# soundcollector.net
KiCad netlist of a schematic drawn in Altium Designer
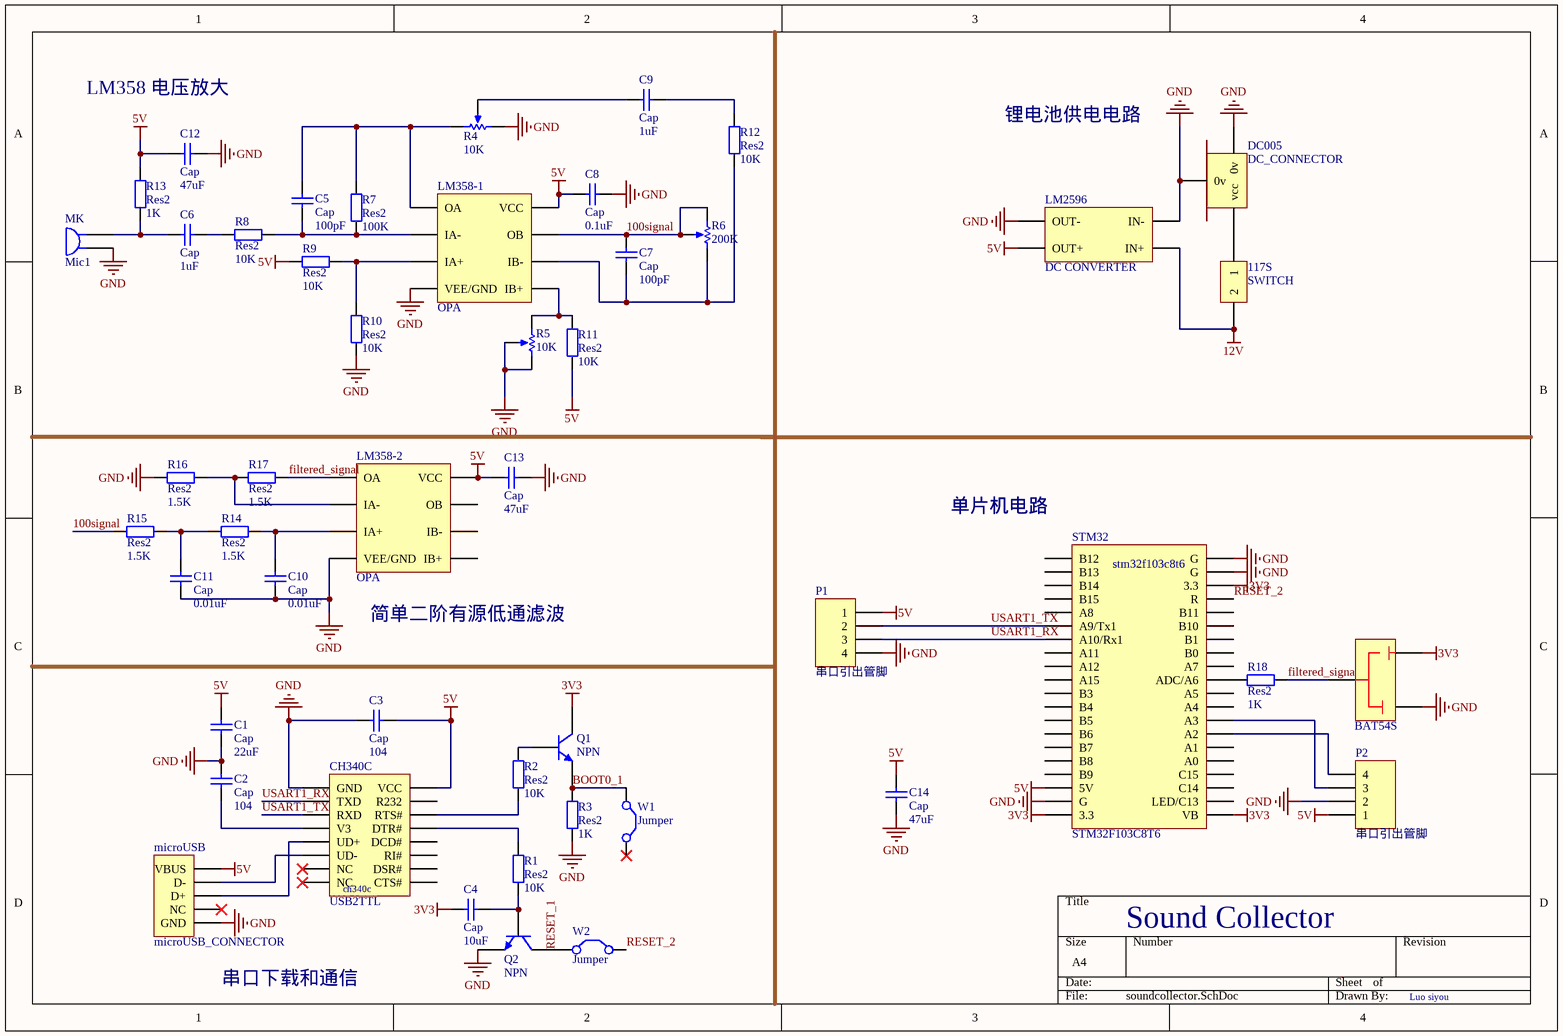
[diagram p0: soundcollector.SchDoc]

(export (version "E")
  (design (tool "Eeschema 10.0.6"))
  (components
    (comp (ref "117S")
      (value "SWITCH")
      (footprint "117S")
      (description "船形开关")
      (libsource (lib "SClib") (part "117S"))
    )
    (comp (ref "BAT54S") (value "BAT54S") (footprint "SOT-23") (libsource (lib "SClib") (part "BAT54S")))
    (comp (ref "C1")
      (value "Cap")
      (footprint "0805")
      (description "Capacitor")
      (fields (field (name "ALTIUM_VALUE") "22uF") (field (name "PUBLISHER") "Altium Limited"))
      (libsource (lib "Miscellaneous Devices") (part "Cap"))
    )
    (comp (ref "C2")
      (value "Cap")
      (footprint "0805")
      (description "Capacitor")
      (fields (field (name "ALTIUM_VALUE") "104") (field (name "PUBLISHER") "Altium Limited"))
      (libsource (lib "Miscellaneous Devices") (part "Cap"))
    )
    (comp (ref "C3")
      (value "Cap")
      (footprint "0805")
      (description "Capacitor")
      (fields (field (name "ALTIUM_VALUE") "104") (field (name "PUBLISHER") "Altium Limited"))
      (libsource (lib "Miscellaneous Devices") (part "Cap"))
    )
    (comp (ref "C4")
      (value "Cap")
      (footprint "0805")
      (description "Capacitor")
      (fields (field (name "ALTIUM_VALUE") "10uF") (field (name "PUBLISHER") "Altium Limited"))
      (libsource (lib "Miscellaneous Devices") (part "Cap"))
    )
    (comp (ref "C5")
      (value "Cap")
      (footprint "0805")
      (description "Capacitor")
      (fields (field (name "ALTIUM_VALUE") "100pF") (field (name "PUBLISHER") "Altium Limited"))
      (libsource (lib "Miscellaneous Devices") (part "Cap"))
    )
    (comp (ref "C6")
      (value "Cap")
      (footprint "0805")
      (description "Capacitor")
      (fields (field (name "ALTIUM_VALUE") "1uF") (field (name "PUBLISHER") "Altium Limited"))
      (libsource (lib "Miscellaneous Devices") (part "Cap"))
    )
    (comp (ref "C7")
      (value "Cap")
      (footprint "0805")
      (description "Capacitor")
      (fields (field (name "ALTIUM_VALUE") "100pF") (field (name "PUBLISHER") "Altium Limited"))
      (libsource (lib "Miscellaneous Devices") (part "Cap"))
    )
    (comp (ref "C8")
      (value "Cap")
      (footprint "0805")
      (description "Capacitor")
      (fields (field (name "ALTIUM_VALUE") "0.1uF") (field (name "PUBLISHER") "Altium Limited"))
      (libsource (lib "Miscellaneous Devices") (part "Cap"))
    )
    (comp (ref "C9")
      (value "Cap")
      (footprint "0805")
      (description "Capacitor")
      (fields (field (name "ALTIUM_VALUE") "1uF") (field (name "PUBLISHER") "Altium Limited"))
      (libsource (lib "Miscellaneous Devices") (part "Cap"))
    )
    (comp (ref "C10")
      (value "Cap")
      (footprint "0805")
      (description "Capacitor")
      (fields (field (name "ALTIUM_VALUE") "0.01uF") (field (name "PUBLISHER") "Altium Limited"))
      (libsource (lib "Miscellaneous Devices") (part "Cap"))
    )
    (comp (ref "C11")
      (value "Cap")
      (footprint "0805")
      (description "Capacitor")
      (fields (field (name "ALTIUM_VALUE") "0.01uF") (field (name "PUBLISHER") "Altium Limited"))
      (libsource (lib "Miscellaneous Devices") (part "Cap"))
    )
    (comp (ref "C12")
      (value "Cap")
      (footprint "0805")
      (description "Capacitor")
      (fields (field (name "ALTIUM_VALUE") "47uF") (field (name "PUBLISHER") "Altium Limited"))
      (libsource (lib "Miscellaneous Devices") (part "Cap"))
    )
    (comp (ref "C13")
      (value "Cap")
      (footprint "0805")
      (description "Capacitor")
      (fields (field (name "ALTIUM_VALUE") "47uF") (field (name "PUBLISHER") "Altium Limited"))
      (libsource (lib "Miscellaneous Devices") (part "Cap"))
    )
    (comp (ref "C14")
      (value "Cap")
      (footprint "0805")
      (description "Capacitor")
      (fields (field (name "ALTIUM_VALUE") "47uF") (field (name "PUBLISHER") "Altium Limited"))
      (libsource (lib "Miscellaneous Devices") (part "Cap"))
    )
    (comp (ref "CH340C")
      (value "USB2TTL")
      (footprint "SOP16")
      (description "电平转换芯片")
      (libsource (lib "SClib") (part "CH340"))
    )
    (comp (ref "DC005")
      (value "DC_CONNECTOR")
      (footprint "DC005")
      (description "直流电源插座")
      (libsource (lib "SClib") (part "DC005"))
    )
    (comp (ref "LM358-1")
      (value "OPA")
      (footprint "SOP-8")
      (description "集成运放")
      (libsource (lib "SClib") (part "LM358"))
    )
    (comp (ref "LM358-2")
      (value "OPA")
      (footprint "SOP-8")
      (description "集成运放")
      (libsource (lib "SClib") (part "LM358"))
    )
    (comp (ref "LM2596")
      (value "DC CONVERTER")
      (footprint "LM2596S")
      (description "直流降压模块")
      (libsource (lib "SClib") (part "LM2596"))
    )
    (comp (ref "microUSB")
      (value "microUSB_CONNECTOR")
      (footprint "MicroUSB-SIP-5")
      (description "将microUSB转换成SIP接口")
      (libsource (lib "SClib") (part "microUSB"))
    )
    (comp (ref "MK")
      (value "Mic1")
      (footprint "PIN2")
      (description "Microphone")
      (fields (field (name "PUBLISHER") "Altium Limited"))
      (libsource (lib "Miscellaneous Devices") (part "Mic1"))
    )
    (comp (ref "P1")
      (value "串口引出管脚")
      (footprint "HDR1X4")
      (description "Header, 4-Pin")
      (fields (field (name "PUBLISHER") "Altium Limited"))
      (libsource (lib "Miscellaneous Connectors") (part "Header 4"))
    )
    (comp (ref "P2")
      (value "串口引出管脚")
      (footprint "HDR1X4")
      (description "Header, 4-Pin")
      (fields (field (name "PUBLISHER") "Altium Limited"))
      (libsource (lib "") (part "Header 4_1"))
    )
    (comp (ref "Q1")
      (value "NPN")
      (footprint "SOT-23")
      (description "NPN三极管")
      (libsource (lib "SClib") (part "S8050"))
    )
    (comp (ref "Q2")
      (value "NPN")
      (footprint "SOT-23")
      (description "NPN三极管")
      (libsource (lib "SClib") (part "S8050"))
    )
    (comp (ref "R1")
      (value "Res2")
      (footprint "0805")
      (description "Resistor")
      (fields (field (name "ALTIUM_VALUE") "10K") (field (name "PUBLISHER") "Altium Limited"))
      (libsource (lib "Miscellaneous Devices") (part "Res2"))
    )
    (comp (ref "R2")
      (value "Res2")
      (footprint "0805")
      (description "Resistor")
      (fields (field (name "ALTIUM_VALUE") "10K") (field (name "PUBLISHER") "Altium Limited"))
      (libsource (lib "Miscellaneous Devices") (part "Res2"))
    )
    (comp (ref "R3")
      (value "Res2")
      (footprint "0805")
      (description "Resistor")
      (fields (field (name "ALTIUM_VALUE") "1K") (field (name "PUBLISHER") "Altium Limited"))
      (libsource (lib "Miscellaneous Devices") (part "Res2"))
    )
    (comp (ref "R4") (value "10K") (footprint "3296W") (libsource (lib "SClib") (part "RPOT")))
    (comp (ref "R5") (value "10K") (footprint "3296W") (libsource (lib "SClib") (part "RPOT")))
    (comp (ref "R6") (value "200K") (footprint "3296W") (libsource (lib "SClib") (part "RPOT")))
    (comp (ref "R7")
      (value "Res2")
      (footprint "0805")
      (description "Resistor")
      (fields (field (name "ALTIUM_VALUE") "100K") (field (name "PUBLISHER") "Altium Limited"))
      (libsource (lib "Miscellaneous Devices") (part "Res2"))
    )
    (comp (ref "R8")
      (value "Res2")
      (footprint "0805")
      (description "Resistor")
      (fields (field (name "ALTIUM_VALUE") "10K") (field (name "PUBLISHER") "Altium Limited"))
      (libsource (lib "Miscellaneous Devices") (part "*"))
    )
    (comp (ref "R9")
      (value "Res2")
      (footprint "0805")
      (description "Resistor")
      (fields (field (name "ALTIUM_VALUE") "10K") (field (name "PUBLISHER") "Altium Limited"))
      (libsource (lib "") (part "Res2_1"))
    )
    (comp (ref "R10")
      (value "Res2")
      (footprint "0805")
      (description "Resistor")
      (fields (field (name "ALTIUM_VALUE") "10K") (field (name "PUBLISHER") "Altium Limited"))
      (libsource (lib "Miscellaneous Devices") (part "Res2"))
    )
    (comp (ref "R11")
      (value "Res2")
      (footprint "0805")
      (description "Resistor")
      (fields (field (name "ALTIUM_VALUE") "10K") (field (name "PUBLISHER") "Altium Limited"))
      (libsource (lib "Miscellaneous Devices") (part "Res2"))
    )
    (comp (ref "R12")
      (value "Res2")
      (footprint "0805")
      (description "Resistor")
      (fields (field (name "ALTIUM_VALUE") "10K") (field (name "PUBLISHER") "Altium Limited"))
      (libsource (lib "Miscellaneous Devices") (part "Res2"))
    )
    (comp (ref "R13")
      (value "Res2")
      (footprint "0805")
      (description "Resistor")
      (fields (field (name "ALTIUM_VALUE") "1K") (field (name "PUBLISHER") "Altium Limited"))
      (libsource (lib "Miscellaneous Devices") (part "Res2"))
    )
    (comp (ref "R14")
      (value "Res2")
      (footprint "0805")
      (description "Resistor")
      (fields (field (name "ALTIUM_VALUE") "1.5K") (field (name "PUBLISHER") "Altium Limited"))
      (libsource (lib "") (part "Res2_2"))
    )
    (comp (ref "R15")
      (value "Res2")
      (footprint "0805")
      (description "Resistor")
      (fields (field (name "ALTIUM_VALUE") "1.5K") (field (name "PUBLISHER") "Altium Limited"))
      (libsource (lib "") (part "Res2_1"))
    )
    (comp (ref "R16")
      (value "Res2")
      (footprint "0805")
      (description "Resistor")
      (fields (field (name "ALTIUM_VALUE") "1.5K") (field (name "PUBLISHER") "Altium Limited"))
      (libsource (lib "") (part "Res2_1"))
    )
    (comp (ref "R17")
      (value "Res2")
      (footprint "0805")
      (description "Resistor")
      (fields (field (name "ALTIUM_VALUE") "1.5K") (field (name "PUBLISHER") "Altium Limited"))
      (libsource (lib "") (part "Res2_2"))
    )
    (comp (ref "R18")
      (value "Res2")
      (footprint "0805")
      (description "Resistor")
      (fields (field (name "ALTIUM_VALUE") "1K") (field (name "PUBLISHER") "Altium Limited"))
      (libsource (lib "") (part "Res2_1"))
    )
    (comp (ref "STM32")
      (value "STM32F103C8T6")
      (footprint "MCU")
      (description "单片机最小系统")
      (libsource (lib "SClib") (part "STM32"))
    )
    (comp (ref "W1")
      (value "Jumper")
      (footprint "HDR1X2")
      (description "Jumper Wire")
      (fields (field (name "PUBLISHER") "Altium Limited"))
      (libsource (lib "Miscellaneous Devices") (part "Jumper"))
    )
    (comp (ref "W2")
      (value "Jumper")
      (footprint "HDR1X2")
      (description "Jumper Wire")
      (fields (field (name "PUBLISHER") "Altium Limited"))
      (libsource (lib "Miscellaneous Devices") (part "Jumper"))
    )
  )
  (nets
    (net (code "1") (name "/100signal") (class "Default")
      (node (ref "C7") (pin "2") (pinfunction "2_2") (pintype "passive"))
      (node (ref "LM358-1") (pin "7") (pinfunction "OB_7") (pintype "passive"))
      (node (ref "R15") (pin "1") (pinfunction "1_1") (pintype "passive"))
      (node (ref "R6") (pin "1") (pinfunction "TOP_1") (pintype "passive"))
      (node (ref "R6") (pin "2") (pinfunction "TAP_2") (pintype "passive"))
    )
    (net (code "2") (name "/BOOT0_1") (class "Default")
      (node (ref "Q1") (pin "2") (pinfunction "E_2") (pintype "passive"))
      (node (ref "R3") (pin "2") (pinfunction "2_2") (pintype "passive"))
      (node (ref "W1") (pin "1") (pinfunction "C1_1") (pintype "passive"))
    )
    (net (code "3") (name "/RESET_1") (class "Default")
      (node (ref "Q2") (pin "3") (pinfunction "C_3") (pintype "passive"))
      (node (ref "W2") (pin "1") (pinfunction "C1_1") (pintype "passive"))
    )
    (net (code "4") (name "/RESET_2") (class "Default")
      (node (ref "STM32") (pin "37") (pinfunction "R_37") (pintype "passive"))
      (node (ref "W2") (pin "2") (pinfunction "C2_2") (pintype "passive"))
    )
    (net (code "5") (name "/USART1_RX") (class "Default")
      (node (ref "CH340C") (pin "2") (pinfunction "TXD_2") (pintype "passive"))
      (node (ref "P1") (pin "3") (pinfunction "3_3") (pintype "passive"))
      (node (ref "STM32") (pin "7") (pinfunction "A10/Rx1_7") (pintype "passive"))
    )
    (net (code "6") (name "/USART1_TX") (class "Default")
      (node (ref "CH340C") (pin "3") (pinfunction "RXD_3") (pintype "passive"))
      (node (ref "P1") (pin "2") (pinfunction "2_2") (pintype "passive"))
      (node (ref "STM32") (pin "6") (pinfunction "A9/Tx1_6") (pintype "passive"))
    )
    (net (code "7") (name "/filtered_signal") (class "Default")
      (node (ref "BAT54S") (pin "3") (pinfunction "series_3") (pintype "passive"))
      (node (ref "LM358-2") (pin "1") (pinfunction "OA_1") (pintype "passive"))
      (node (ref "R17") (pin "1") (pinfunction "1_1") (pintype "passive"))
      (node (ref "R18") (pin "2") (pinfunction "2_2") (pintype "passive"))
    )
    (net (code "8") (name "3V3") (class "Default")
      (node (ref "BAT54S") (pin "2") (pinfunction "VCC_2") (pintype "passive"))
      (node (ref "C4") (pin "1") (pinfunction "1_1") (pintype "passive"))
      (node (ref "Q1") (pin "3") (pinfunction "C_3") (pintype "passive"))
      (node (ref "STM32") (pin "20") (pinfunction "3.3_20") (pintype "passive"))
      (node (ref "STM32") (pin "21") (pinfunction "VB_21") (pintype "passive"))
      (node (ref "STM32") (pin "38") (pinfunction "3.3_38") (pintype "passive"))
    )
    (net (code "9") (name "5V") (class "Default")
      (node (ref "C1") (pin "2") (pinfunction "2_2") (pintype "passive"))
      (node (ref "C12") (pin "1") (pinfunction "1_1") (pintype "passive"))
      (node (ref "C13") (pin "1") (pinfunction "1_1") (pintype "passive"))
      (node (ref "C14") (pin "2") (pinfunction "2_2") (pintype "passive"))
      (node (ref "C3") (pin "2") (pinfunction "2_2") (pintype "passive"))
      (node (ref "C8") (pin "1") (pinfunction "1_1") (pintype "passive"))
      (node (ref "CH340C") (pin "16") (pinfunction "VCC_16") (pintype "passive"))
      (node (ref "LM2596") (pin "3") (pinfunction "OUT+_3") (pintype "passive"))
      (node (ref "LM358-1") (pin "8") (pinfunction "VCC_8") (pintype "passive"))
      (node (ref "LM358-2") (pin "8") (pinfunction "VCC_8") (pintype "passive"))
      (node (ref "P1") (pin "1") (pinfunction "1_1") (pintype "passive"))
      (node (ref "P2") (pin "1") (pinfunction "1_1") (pintype "passive"))
      (node (ref "R11") (pin "1") (pinfunction "1_1") (pintype "passive"))
      (node (ref "R13") (pin "2") (pinfunction "2_2") (pintype "passive"))
      (node (ref "R9") (pin "1") (pinfunction "1_1") (pintype "passive"))
      (node (ref "STM32") (pin "18") (pinfunction "5V_18") (pintype "passive"))
      (node (ref "microUSB") (pin "1") (pinfunction "VBUS_1") (pintype "passive"))
    )
    (net (code "10") (name "12V") (class "Default")
      (node (ref "117S") (pin "2") (pinfunction "2_2") (pintype "passive"))
      (node (ref "LM2596") (pin "2") (pinfunction "IN+_2") (pintype "passive"))
    )
    (net (code "11") (name "GND") (class "Default")
      (node (ref "BAT54S") (pin "1") (pinfunction "GND_1") (pintype "passive"))
      (node (ref "C1") (pin "1") (pinfunction "1_1") (pintype "passive"))
      (node (ref "C10") (pin "1") (pinfunction "1_1") (pintype "passive"))
      (node (ref "C11") (pin "1") (pinfunction "1_1") (pintype "passive"))
      (node (ref "C12") (pin "2") (pinfunction "2_2") (pintype "passive"))
      (node (ref "C13") (pin "2") (pinfunction "2_2") (pintype "passive"))
      (node (ref "C14") (pin "1") (pinfunction "1_1") (pintype "passive"))
      (node (ref "C2") (pin "2") (pinfunction "2_2") (pintype "passive"))
      (node (ref "C3") (pin "1") (pinfunction "1_1") (pintype "passive"))
      (node (ref "C8") (pin "2") (pinfunction "2_2") (pintype "passive"))
      (node (ref "CH340C") (pin "1") (pinfunction "GND_1") (pintype "passive"))
      (node (ref "DC005") (pin "1") (pinfunction "0v_1") (pintype "passive"))
      (node (ref "DC005") (pin "2") (pinfunction "0v_2") (pintype "passive"))
      (node (ref "LM2596") (pin "1") (pinfunction "IN-_1") (pintype "passive"))
      (node (ref "LM2596") (pin "4") (pinfunction "OUT-_4") (pintype "passive"))
      (node (ref "LM358-1") (pin "4") (pinfunction "VEE/GND_4") (pintype "passive"))
      (node (ref "LM358-2") (pin "4") (pinfunction "VEE/GND_4") (pintype "passive"))
      (node (ref "MK") (pin "1") (pinfunction "1_1") (pintype "passive"))
      (node (ref "P1") (pin "4") (pinfunction "4_4") (pintype "passive"))
      (node (ref "P2") (pin "2") (pinfunction "2_2") (pintype "passive"))
      (node (ref "Q2") (pin "2") (pinfunction "E_2") (pintype "passive"))
      (node (ref "R10") (pin "1") (pinfunction "1_1") (pintype "passive"))
      (node (ref "R16") (pin "1") (pinfunction "1_1") (pintype "passive"))
      (node (ref "R3") (pin "1") (pinfunction "1_1") (pintype "passive"))
      (node (ref "R4") (pin "1") (pinfunction "TOP_1") (pintype "passive"))
      (node (ref "R5") (pin "2") (pinfunction "TAP_2") (pintype "passive"))
      (node (ref "R5") (pin "3") (pinfunction "BOT_3") (pintype "passive"))
      (node (ref "STM32") (pin "19") (pinfunction "G_19") (pintype "passive"))
      (node (ref "STM32") (pin "39") (pinfunction "G_39") (pintype "passive"))
      (node (ref "STM32") (pin "40") (pinfunction "G_40") (pintype "passive"))
      (node (ref "microUSB") (pin "5") (pinfunction "GND_5") (pintype "passive"))
    )
    (net (code "12") (name "Net-(C6-Pad1)") (class "Default")
      (node (ref "C6") (pin "1") (pinfunction "1_1") (pintype "passive"))
      (node (ref "MK") (pin "2") (pinfunction "2_2") (pintype "passive"))
      (node (ref "R13") (pin "1") (pinfunction "1_1") (pintype "passive"))
    )
    (net (code "13") (name "Net-(C6-Pad2)") (class "Default")
      (node (ref "C6") (pin "2") (pinfunction "2_2") (pintype "passive"))
      (node (ref "R8") (pin "1") (pinfunction "1_1") (pintype "passive"))
    )
    (net (code "14") (name "Net-(C9-Pad2)") (class "Default")
      (node (ref "C9") (pin "2") (pinfunction "2_2") (pintype "passive"))
      (node (ref "R12") (pin "2") (pinfunction "2_2") (pintype "passive"))
    )
    (net (code "15") (name "Net-(C11-Pad2)") (class "Default")
      (node (ref "C11") (pin "2") (pinfunction "2_2") (pintype "passive"))
      (node (ref "R14") (pin "2") (pinfunction "2_2") (pintype "passive"))
      (node (ref "R15") (pin "2") (pinfunction "2_2") (pintype "passive"))
    )
    (net (code "16") (name "Net-(CH340C-DTR#)") (class "Default")
      (node (ref "CH340C") (pin "13") (pinfunction "DTR#_13") (pintype "passive"))
      (node (ref "R1") (pin "2") (pinfunction "2_2") (pintype "passive"))
    )
    (net (code "17") (name "Net-(CH340C-RTS#)") (class "Default")
      (node (ref "CH340C") (pin "14") (pinfunction "RTS#_14") (pintype "passive"))
      (node (ref "R2") (pin "1") (pinfunction "1_1") (pintype "passive"))
    )
    (net (code "18") (name "Net-(CH340C-UD+)") (class "Default")
      (node (ref "CH340C") (pin "5") (pinfunction "UD+_5") (pintype "passive"))
      (node (ref "microUSB") (pin "3") (pinfunction "D+_3") (pintype "passive"))
    )
    (net (code "19") (name "Net-(CH340C-UD-)") (class "Default")
      (node (ref "CH340C") (pin "6") (pinfunction "UD-_6") (pintype "passive"))
      (node (ref "microUSB") (pin "2") (pinfunction "D-_2") (pintype "passive"))
    )
    (net (code "20") (name "Net-(CH340C-V3)") (class "Default")
      (node (ref "C2") (pin "1") (pinfunction "1_1") (pintype "passive"))
      (node (ref "CH340C") (pin "4") (pinfunction "V3_4") (pintype "passive"))
    )
    (net (code "21") (name "Net-(DC005-vcc)") (class "Default")
      (node (ref "117S") (pin "1") (pinfunction "1_1") (pintype "passive"))
      (node (ref "DC005") (pin "3") (pinfunction "vcc_3") (pintype "passive"))
    )
    (net (code "22") (name "Net-(LM358-1-IA+)") (class "Default")
      (node (ref "LM358-1") (pin "3") (pinfunction "IA+_3") (pintype "passive"))
      (node (ref "R10") (pin "2") (pinfunction "2_2") (pintype "passive"))
      (node (ref "R9") (pin "2") (pinfunction "2_2") (pintype "passive"))
    )
    (net (code "23") (name "Net-(LM358-1-IA-)") (class "Default")
      (node (ref "C5") (pin "1") (pinfunction "1_1") (pintype "passive"))
      (node (ref "LM358-1") (pin "2") (pinfunction "IA-_2") (pintype "passive"))
      (node (ref "R7") (pin "1") (pinfunction "1_1") (pintype "passive"))
      (node (ref "R8") (pin "2") (pinfunction "2_2") (pintype "passive"))
    )
    (net (code "24") (name "Net-(LM358-1-IB+)") (class "Default")
      (node (ref "LM358-1") (pin "5") (pinfunction "IB+_5") (pintype "passive"))
      (node (ref "R11") (pin "2") (pinfunction "2_2") (pintype "passive"))
      (node (ref "R5") (pin "1") (pinfunction "TOP_1") (pintype "passive"))
    )
    (net (code "25") (name "Net-(LM358-1-IB-)") (class "Default")
      (node (ref "C7") (pin "1") (pinfunction "1_1") (pintype "passive"))
      (node (ref "LM358-1") (pin "6") (pinfunction "IB-_6") (pintype "passive"))
      (node (ref "R12") (pin "1") (pinfunction "1_1") (pintype "passive"))
      (node (ref "R6") (pin "3") (pinfunction "BOT_3") (pintype "passive"))
    )
    (net (code "26") (name "Net-(LM358-1-OA)") (class "Default")
      (node (ref "C5") (pin "2") (pinfunction "2_2") (pintype "passive"))
      (node (ref "LM358-1") (pin "1") (pinfunction "OA_1") (pintype "passive"))
      (node (ref "R4") (pin "3") (pinfunction "BOT_3") (pintype "passive"))
      (node (ref "R7") (pin "2") (pinfunction "2_2") (pintype "passive"))
    )
    (net (code "27") (name "Net-(LM358-2-IA+)") (class "Default")
      (node (ref "C10") (pin "2") (pinfunction "2_2") (pintype "passive"))
      (node (ref "LM358-2") (pin "3") (pinfunction "IA+_3") (pintype "passive"))
      (node (ref "R14") (pin "1") (pinfunction "1_1") (pintype "passive"))
    )
    (net (code "28") (name "Net-(LM358-2-IA-)") (class "Default")
      (node (ref "LM358-2") (pin "2") (pinfunction "IA-_2") (pintype "passive"))
      (node (ref "R16") (pin "2") (pinfunction "2_2") (pintype "passive"))
      (node (ref "R17") (pin "2") (pinfunction "2_2") (pintype "passive"))
    )
    (net (code "29") (name "Net-(Q1-B)") (class "Default")
      (node (ref "Q1") (pin "1") (pinfunction "B_1") (pintype "passive"))
      (node (ref "R2") (pin "2") (pinfunction "2_2") (pintype "passive"))
    )
    (net (code "30") (name "Net-(Q2-B)") (class "Default")
      (node (ref "C4") (pin "2") (pinfunction "2_2") (pintype "passive"))
      (node (ref "Q2") (pin "1") (pinfunction "B_1") (pintype "passive"))
      (node (ref "R1") (pin "1") (pinfunction "1_1") (pintype "passive"))
    )
    (net (code "31") (name "Net-(R4-TAP)") (class "Default")
      (node (ref "C9") (pin "1") (pinfunction "1_1") (pintype "passive"))
      (node (ref "R4") (pin "2") (pinfunction "TAP_2") (pintype "passive"))
    )
    (net (code "32") (name "Net-(STM32-A2)") (class "Default")
      (node (ref "P2") (pin "4") (pinfunction "4_4") (pintype "passive"))
      (node (ref "STM32") (pin "27") (pinfunction "A2_27") (pintype "passive"))
    )
    (net (code "33") (name "Net-(STM32-A3)") (class "Default")
      (node (ref "P2") (pin "3") (pinfunction "3_3") (pintype "passive"))
      (node (ref "STM32") (pin "28") (pinfunction "A3_28") (pintype "passive"))
    )
    (net (code "34") (name "Net-(STM32-ADC{slash}A6)") (class "Default")
      (node (ref "R18") (pin "1") (pinfunction "1_1") (pintype "passive"))
      (node (ref "STM32") (pin "31") (pinfunction "ADC/A6_31") (pintype "passive"))
    )
    (net (code "35") (name "unconnected-(CH340C-CTS#-Pad9)") (class "Default")
      (node (ref "CH340C") (pin "9") (pinfunction "CTS#_9") (pintype "passive"))
    )
    (net (code "36") (name "unconnected-(CH340C-DCD#-Pad12)") (class "Default")
      (node (ref "CH340C") (pin "12") (pinfunction "DCD#_12") (pintype "passive"))
    )
    (net (code "37") (name "unconnected-(CH340C-DSR#-Pad10)") (class "Default")
      (node (ref "CH340C") (pin "10") (pinfunction "DSR#_10") (pintype "passive"))
    )
    (net (code "38") (name "unconnected-(CH340C-NC-Pad7)") (class "Default")
      (node (ref "CH340C") (pin "7") (pinfunction "NC_7") (pintype "passive+no_connect"))
    )
    (net (code "39") (name "unconnected-(CH340C-NC-Pad8)") (class "Default")
      (node (ref "CH340C") (pin "8") (pinfunction "NC_8") (pintype "passive+no_connect"))
    )
    (net (code "40") (name "unconnected-(CH340C-R232-Pad15)") (class "Default")
      (node (ref "CH340C") (pin "15") (pinfunction "R232_15") (pintype "passive"))
    )
    (net (code "41") (name "unconnected-(CH340C-RI#-Pad11)") (class "Default")
      (node (ref "CH340C") (pin "11") (pinfunction "RI#_11") (pintype "passive"))
    )
    (net (code "42") (name "unconnected-(LM358-2-IB+-Pad5)") (class "Default")
      (node (ref "LM358-2") (pin "5") (pinfunction "IB+_5") (pintype "passive"))
    )
    (net (code "43") (name "unconnected-(LM358-2-IB--Pad6)") (class "Default")
      (node (ref "LM358-2") (pin "6") (pinfunction "IB-_6") (pintype "passive"))
    )
    (net (code "44") (name "unconnected-(LM358-2-OB-Pad7)") (class "Default")
      (node (ref "LM358-2") (pin "7") (pinfunction "OB_7") (pintype "passive"))
    )
    (net (code "45") (name "unconnected-(STM32-A0-Pad25)") (class "Default")
      (node (ref "STM32") (pin "25") (pinfunction "A0_25") (pintype "passive"))
    )
    (net (code "46") (name "unconnected-(STM32-A1-Pad26)") (class "Default")
      (node (ref "STM32") (pin "26") (pinfunction "A1_26") (pintype "passive"))
    )
    (net (code "47") (name "unconnected-(STM32-A4-Pad29)") (class "Default")
      (node (ref "STM32") (pin "29") (pinfunction "A4_29") (pintype "passive"))
    )
    (net (code "48") (name "unconnected-(STM32-A5-Pad30)") (class "Default")
      (node (ref "STM32") (pin "30") (pinfunction "A5_30") (pintype "passive"))
    )
    (net (code "49") (name "unconnected-(STM32-A7-Pad32)") (class "Default")
      (node (ref "STM32") (pin "32") (pinfunction "A7_32") (pintype "passive"))
    )
    (net (code "50") (name "unconnected-(STM32-A8-Pad5)") (class "Default")
      (node (ref "STM32") (pin "5") (pinfunction "A8_5") (pintype "passive"))
    )
    (net (code "51") (name "unconnected-(STM32-A11-Pad8)") (class "Default")
      (node (ref "STM32") (pin "8") (pinfunction "A11_8") (pintype "passive"))
    )
    (net (code "52") (name "unconnected-(STM32-A12-Pad9)") (class "Default")
      (node (ref "STM32") (pin "9") (pinfunction "A12_9") (pintype "passive"))
    )
    (net (code "53") (name "unconnected-(STM32-A15-Pad10)") (class "Default")
      (node (ref "STM32") (pin "10") (pinfunction "A15_10") (pintype "passive"))
    )
    (net (code "54") (name "unconnected-(STM32-B0-Pad33)") (class "Default")
      (node (ref "STM32") (pin "33") (pinfunction "B0_33") (pintype "passive"))
    )
    (net (code "55") (name "unconnected-(STM32-B1-Pad34)") (class "Default")
      (node (ref "STM32") (pin "34") (pinfunction "B1_34") (pintype "passive"))
    )
    (net (code "56") (name "unconnected-(STM32-B3-Pad11)") (class "Default")
      (node (ref "STM32") (pin "11") (pinfunction "B3_11") (pintype "passive"))
    )
    (net (code "57") (name "unconnected-(STM32-B4-Pad12)") (class "Default")
      (node (ref "STM32") (pin "12") (pinfunction "B4_12") (pintype "passive"))
    )
    (net (code "58") (name "unconnected-(STM32-B5-Pad13)") (class "Default")
      (node (ref "STM32") (pin "13") (pinfunction "B5_13") (pintype "passive"))
    )
    (net (code "59") (name "unconnected-(STM32-B6-Pad14)") (class "Default")
      (node (ref "STM32") (pin "14") (pinfunction "B6_14") (pintype "passive"))
    )
    (net (code "60") (name "unconnected-(STM32-B7-Pad15)") (class "Default")
      (node (ref "STM32") (pin "15") (pinfunction "B7_15") (pintype "passive"))
    )
    (net (code "61") (name "unconnected-(STM32-B8-Pad16)") (class "Default")
      (node (ref "STM32") (pin "16") (pinfunction "B8_16") (pintype "passive"))
    )
    (net (code "62") (name "unconnected-(STM32-B9-Pad17)") (class "Default")
      (node (ref "STM32") (pin "17") (pinfunction "B9_17") (pintype "passive"))
    )
    (net (code "63") (name "unconnected-(STM32-B10-Pad35)") (class "Default")
      (node (ref "STM32") (pin "35") (pinfunction "B10_35") (pintype "passive"))
    )
    (net (code "64") (name "unconnected-(STM32-B11-Pad36)") (class "Default")
      (node (ref "STM32") (pin "36") (pinfunction "B11_36") (pintype "passive"))
    )
    (net (code "65") (name "unconnected-(STM32-B12-Pad1)") (class "Default")
      (node (ref "STM32") (pin "1") (pinfunction "B12_1") (pintype "passive"))
    )
    (net (code "66") (name "unconnected-(STM32-B13-Pad2)") (class "Default")
      (node (ref "STM32") (pin "2") (pinfunction "B13_2") (pintype "passive"))
    )
    (net (code "67") (name "unconnected-(STM32-B14-Pad3)") (class "Default")
      (node (ref "STM32") (pin "3") (pinfunction "B14_3") (pintype "passive"))
    )
    (net (code "68") (name "unconnected-(STM32-B15-Pad4)") (class "Default")
      (node (ref "STM32") (pin "4") (pinfunction "B15_4") (pintype "passive"))
    )
    (net (code "69") (name "unconnected-(STM32-C14-Pad23)") (class "Default")
      (node (ref "STM32") (pin "23") (pinfunction "C14_23") (pintype "passive"))
    )
    (net (code "70") (name "unconnected-(STM32-C15-Pad24)") (class "Default")
      (node (ref "STM32") (pin "24") (pinfunction "C15_24") (pintype "passive"))
    )
    (net (code "71") (name "unconnected-(STM32-LED{slash}C13-Pad22)") (class "Default")
      (node (ref "STM32") (pin "22") (pinfunction "LED/C13_22") (pintype "passive"))
    )
    (net (code "72") (name "unconnected-(W1-C2-Pad2)") (class "Default")
      (node (ref "W1") (pin "2") (pinfunction "C2_2") (pintype "passive+no_connect"))
    )
    (net (code "73") (name "unconnected-(microUSB-NC-Pad4)") (class "Default")
      (node (ref "microUSB") (pin "4") (pinfunction "NC_4") (pintype "passive+no_connect"))
    )
  )
)
